# Filter.net
KiCad netlist of a schematic drawn in Altium Designer
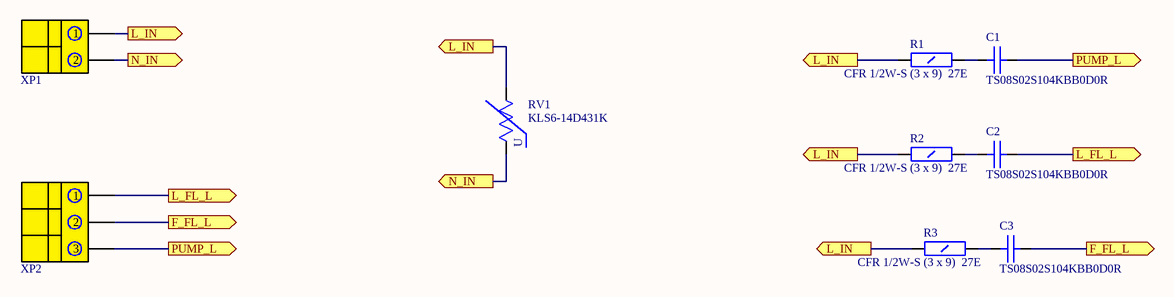
[diagram p0: Filter.SchDoc]

(export (version "E")
  (design (tool "Eeschema 10.0.6"))
  (components
    (comp (ref "C1")
      (value "TS08S02S104KBB0D0R")
      (footprint "CAP_HV_13x5")
      (libsource (lib "fizik_lib") (part "CAP_HV_13x5"))
    )
    (comp (ref "C2")
      (value "TS08S02S104KBB0D0R")
      (footprint "CAP_HV_13x5")
      (libsource (lib "fizik_lib") (part "CAP_HV_13x5"))
    )
    (comp (ref "C3")
      (value "TS08S02S104KBB0D0R")
      (footprint "CAP_HV_13x5")
      (libsource (lib "fizik_lib") (part "CAP_HV_13x5"))
    )
    (comp (ref "R1")
      (value "СFR 1/2W-S (3 x 9)  27E")
      (footprint "RES_10x4_THD")
      (description "THR resisto r10x3mm 0.5W")
      (libsource (lib "fizik_lib") (part "RC_1003_THR"))
    )
    (comp (ref "R2")
      (value "СFR 1/2W-S (3 x 9)  27E")
      (footprint "RES_10x4_THD")
      (description "THR resisto r10x3mm 0.5W")
      (libsource (lib "fizik_lib") (part "RC_1003_THR"))
    )
    (comp (ref "R3")
      (value "СFR 1/2W-S (3 x 9)  27E")
      (footprint "RES_10x4_THD")
      (description "THR resisto r10x3mm 0.5W")
      (libsource (lib "fizik_lib") (part "RC_1003_THR"))
    )
    (comp (ref "RV1")
      (value "KLS6-14D431K")
      (footprint "Varistor_14MM")
      (description "Varistor diameter 14mm")
      (libsource (lib "fizik_lib") (part "KLS6-14D431K"))
    )
    (comp (ref "XP1")
      (value "DG330-2P")
      (footprint "DG330-2P")
      (description "Degson 2 pin connector rear")
      (libsource (lib "fizik_lib") (part "DG330-2P"))
    )
    (comp (ref "XP2")
      (value "DG330-3PIN")
      (footprint "DG330-3P")
      (description "Degson 3 pin connector rear")
      (libsource (lib "fizik_lib") (part "DG330-3P"))
    )
  )
  (nets
    (net (code "1") (name "/F_FL_L") (class "Default")
      (node (ref "C3") (pin "2") (pinfunction "B_2") (pintype "passive"))
      (node (ref "XP2") (pin "2") (pinfunction "2_2") (pintype "passive"))
    )
    (net (code "2") (name "/L_FL_L") (class "Default")
      (node (ref "C2") (pin "2") (pinfunction "B_2") (pintype "passive"))
      (node (ref "XP2") (pin "1") (pinfunction "1_1") (pintype "passive"))
    )
    (net (code "3") (name "/L_IN") (class "Default")
      (node (ref "R1") (pin "2") (pinfunction "B_2") (pintype "passive"))
      (node (ref "R2") (pin "2") (pinfunction "B_2") (pintype "passive"))
      (node (ref "R3") (pin "2") (pinfunction "B_2") (pintype "passive"))
      (node (ref "RV1") (pin "2") (pinfunction "B_2") (pintype "passive"))
      (node (ref "XP1") (pin "1") (pinfunction "1_1") (pintype "passive"))
    )
    (net (code "4") (name "/N_IN") (class "Default")
      (node (ref "RV1") (pin "1") (pinfunction "A_1") (pintype "passive"))
      (node (ref "XP1") (pin "2") (pinfunction "2_2") (pintype "passive"))
    )
    (net (code "5") (name "/PUMP_L") (class "Default")
      (node (ref "C1") (pin "2") (pinfunction "B_2") (pintype "passive"))
      (node (ref "XP2") (pin "3") (pinfunction "3_3") (pintype "passive"))
    )
    (net (code "6") (name "Net-(C1-A)") (class "Default")
      (node (ref "C1") (pin "1") (pinfunction "A_1") (pintype "passive"))
      (node (ref "R1") (pin "1") (pinfunction "A_1") (pintype "passive"))
    )
    (net (code "7") (name "Net-(C2-A)") (class "Default")
      (node (ref "C2") (pin "1") (pinfunction "A_1") (pintype "passive"))
      (node (ref "R2") (pin "1") (pinfunction "A_1") (pintype "passive"))
    )
    (net (code "8") (name "Net-(C3-A)") (class "Default")
      (node (ref "C3") (pin "1") (pinfunction "A_1") (pintype "passive"))
      (node (ref "R3") (pin "1") (pinfunction "A_1") (pintype "passive"))
    )
  )
)
